# pickit.net
KiCad netlist of a schematic drawn in Altium Designer
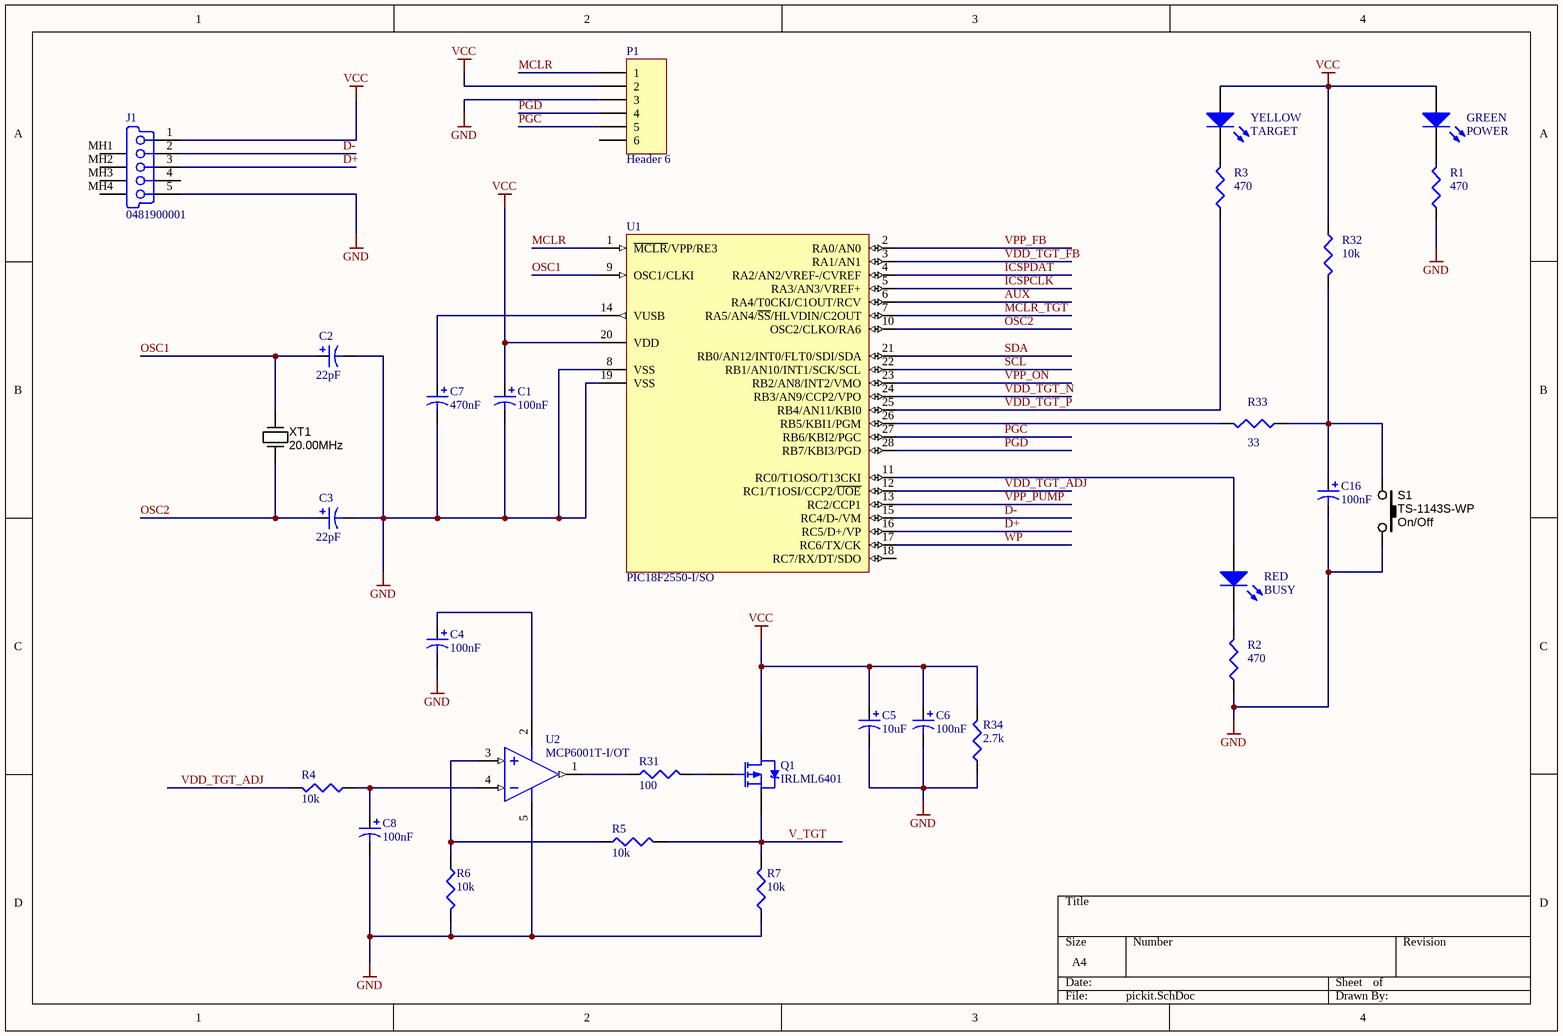
[diagram p0: pickit.SchDoc]

(export (version "E")
  (design (tool "Eeschema 10.0.6"))
  (components
    (comp (ref "C1")
      (value "100nF")
      (footprint "C0805")
      (description "Polarized Capacitor (Surface Mount)")
      (fields (field (name "Comment") "Cap Pol3") (field (name "PUBLISHER") "Altium Limited"))
      (libsource (lib "Miscellaneous Devices") (part "Cap Pol3"))
    )
    (comp (ref "C2")
      (value "22pF")
      (footprint "C0805")
      (description "Polarized Capacitor (Surface Mount)")
      (fields (field (name "Comment") "Cap Pol3") (field (name "PUBLISHER") "Altium Limited"))
      (libsource (lib "Miscellaneous Devices") (part "Cap Pol3"))
    )
    (comp (ref "C3")
      (value "22pF")
      (footprint "C0805")
      (description "Polarized Capacitor (Surface Mount)")
      (fields (field (name "Comment") "Cap Pol3") (field (name "PUBLISHER") "Altium Limited"))
      (libsource (lib "Miscellaneous Devices") (part "Cap Pol3"))
    )
    (comp (ref "C4")
      (value "100nF")
      (footprint "C0805")
      (description "Polarized Capacitor (Surface Mount)")
      (fields (field (name "Comment") "Cap Pol3") (field (name "PUBLISHER") "Altium Limited"))
      (libsource (lib "Miscellaneous Devices") (part "Cap Pol3"))
    )
    (comp (ref "C5")
      (value "10uF")
      (footprint "C0805")
      (description "Polarized Capacitor (Surface Mount)")
      (fields (field (name "Comment") "Cap Pol3") (field (name "PUBLISHER") "Altium Limited"))
      (libsource (lib "Miscellaneous Devices") (part "Cap Pol3"))
    )
    (comp (ref "C6")
      (value "100nF")
      (footprint "C0805")
      (description "Polarized Capacitor (Surface Mount)")
      (fields (field (name "Comment") "Cap Pol3") (field (name "PUBLISHER") "Altium Limited"))
      (libsource (lib "Miscellaneous Devices") (part "Cap Pol3"))
    )
    (comp (ref "C7")
      (value "470nF")
      (footprint "C0805")
      (description "Polarized Capacitor (Surface Mount)")
      (fields (field (name "Comment") "Cap Pol3") (field (name "PUBLISHER") "Altium Limited"))
      (libsource (lib "Miscellaneous Devices") (part "Cap Pol3"))
    )
    (comp (ref "C8")
      (value "100nF")
      (footprint "C0805")
      (description "Polarized Capacitor (Surface Mount)")
      (fields (field (name "Comment") "Cap Pol3") (field (name "PUBLISHER") "Altium Limited"))
      (libsource (lib "Miscellaneous Devices") (part "Cap Pol3"))
    )
    (comp (ref "C16")
      (value "100nF")
      (footprint "C0805")
      (description "Polarized Capacitor (Surface Mount)")
      (fields (field (name "Comment") "Cap Pol3") (field (name "PUBLISHER") "Altium Limited"))
      (libsource (lib "Miscellaneous Devices") (part "Cap Pol3"))
    )
    (comp (ref "GREEN")
      (value "POWER")
      (footprint "3.5X2.8X1.9")
      (description "Typical BLUE SiC LED")
      (fields (field (name "PUBLISHER") "Altium Limited"))
      (libsource (lib "Miscellaneous Devices") (part "LED3"))
    )
    (comp (ref "J1")
      (value "0481900001")
      (footprint "481900001")
      (fields (field (name "PUBLISHER") "Altium Limited"))
      (libsource (lib "Molex Serial Bus Mini USB") (part "0481900001"))
    )
    (comp (ref "P1")
      (value "Header 6")
      (footprint "HDR1X6")
      (description "Header, 6-Pin")
      (fields (field (name "PUBLISHER") "Altium Limited"))
      (libsource (lib "Miscellaneous Connectors") (part "Header 6"))
    )
    (comp (ref "Q1")
      (value "IRLML6401")
      (footprint "Micro3_N")
      (description "HEXFET Power MOSFET")
      (fields (field (name "PUBLISHER") "Altium Limited"))
      (libsource (lib "IR Discrete MOSFET - Power") (part "IRLML6401"))
    )
    (comp (ref "R1")
      (value "470")
      (footprint "RESC2012X70N")
      (description "Resistor")
      (fields (field (name "Comment") "Res3") (field (name "PUBLISHER") "Altium Limited"))
      (libsource (lib "Miscellaneous Devices") (part "Res3"))
    )
    (comp (ref "R2")
      (value "470")
      (footprint "RESC2012X70N")
      (description "Resistor")
      (fields (field (name "Comment") "Res3") (field (name "PUBLISHER") "Altium Limited"))
      (libsource (lib "Miscellaneous Devices") (part "Res3"))
    )
    (comp (ref "R3")
      (value "470")
      (footprint "RESC2012X70N")
      (description "Resistor")
      (fields (field (name "Comment") "Res3") (field (name "PUBLISHER") "Altium Limited"))
      (libsource (lib "Miscellaneous Devices") (part "Res3"))
    )
    (comp (ref "R4")
      (value "10k")
      (footprint "RESC2012X70N")
      (description "Resistor")
      (fields (field (name "Comment") "Res3") (field (name "PUBLISHER") "Altium Limited"))
      (libsource (lib "Miscellaneous Devices") (part "Res3"))
    )
    (comp (ref "R5")
      (value "10k")
      (footprint "RESC2012X70N")
      (description "Resistor")
      (fields (field (name "Comment") "Res3") (field (name "PUBLISHER") "Altium Limited"))
      (libsource (lib "Miscellaneous Devices") (part "Res3"))
    )
    (comp (ref "R6")
      (value "10k")
      (footprint "RESC2012X70N")
      (description "Resistor")
      (fields (field (name "Comment") "Res3") (field (name "PUBLISHER") "Altium Limited"))
      (libsource (lib "Miscellaneous Devices") (part "Res3"))
    )
    (comp (ref "R7")
      (value "10k")
      (footprint "RESC2012X70N")
      (description "Resistor")
      (fields (field (name "Comment") "Res3") (field (name "PUBLISHER") "Altium Limited"))
      (libsource (lib "Miscellaneous Devices") (part "Res3"))
    )
    (comp (ref "R31")
      (value "100")
      (footprint "RESC2012X70N")
      (description "Resistor")
      (fields (field (name "Comment") "Res3") (field (name "PUBLISHER") "Altium Limited"))
      (libsource (lib "Miscellaneous Devices") (part "Res3"))
    )
    (comp (ref "R32")
      (value "10k")
      (footprint "RESC2012X70N")
      (description "Resistor")
      (fields (field (name "Comment") "Res3") (field (name "PUBLISHER") "Altium Limited"))
      (libsource (lib "Miscellaneous Devices") (part "Res3"))
    )
    (comp (ref "R33")
      (value "33")
      (footprint "RESC2012X70N")
      (description "Resistor")
      (fields (field (name "Comment") "Res3") (field (name "PUBLISHER") "Altium Limited"))
      (libsource (lib "Miscellaneous Devices") (part "Res3"))
    )
    (comp (ref "R34")
      (value "2.7k")
      (footprint "RESC2012X70N")
      (description "Resistor")
      (fields (field (name "Comment") "Res3") (field (name "PUBLISHER") "Altium Limited"))
      (libsource (lib "Miscellaneous Devices") (part "Res3"))
    )
    (comp (ref "RED")
      (value "BUSY")
      (footprint "3.5X2.8X1.9")
      (description "Typical BLUE SiC LED")
      (fields (field (name "PUBLISHER") "Altium Limited"))
      (libsource (lib "Miscellaneous Devices") (part "LED3"))
    )
    (comp (ref "S1")
      (value "TS-1143S-WP")
      (footprint "TS-1143S")
      (description "Switch SMD Tact 4.3mm Stem")
      (fields (field (name "FUNCTION") "On/Off"))
      (libsource (lib "PBL - Switches") (part "SW_SMD_PB_4.3mm"))
    )
    (comp (ref "U1")
      (value "PIC18F2550-I/SO")
      (footprint "SOIC-SO28_N")
      (fields (field (name "PUBLISHER") "Altium Limited"))
      (libsource (lib "Microchip Microcontroller 8-Bit PIC18") (part "PIC18F2550-I/SO"))
    )
    (comp (ref "U2")
      (value "MCP6001T-I/OT")
      (footprint "SOT-23-OT5_N")
      (description "1 MHz, Low-Power Operational Amplifier, 5-Pin SOT-23, Industrial Temperature, Tape and Reel")
      (fields (field (name "PUBLISHER") "Altium Limited"))
      (libsource (lib "Microchip Linear Devices") (part "MCP6001T-I/OT"))
    )
    (comp (ref "XT1")
      (value "20.00MHz")
      (footprint "CRYSTAL_HC49-US-SM")
      (description "Resonator Ceramic 6.00 MHz 30ppm")
      (libsource (lib "PBL - Resonators") (part "Crystal_6MHz_HC49/US"))
    )
    (comp (ref "YELLOW")
      (value "TARGET")
      (footprint "3.5X2.8X1.9")
      (description "Typical BLUE SiC LED")
      (fields (field (name "PUBLISHER") "Altium Limited"))
      (libsource (lib "Miscellaneous Devices") (part "LED3"))
    )
  )
  (nets
    (net (code "1") (name "/AUX") (class "Default")
      (node (ref "U1") (pin "6") (pinfunction "RA4/T0CKI/C1OUT/RCV_6") (pintype "bidirectional"))
    )
    (net (code "2") (name "/D+") (class "Default")
      (node (ref "J1") (pin "3") (pinfunction "D+_3") (pintype "passive"))
      (node (ref "U1") (pin "16") (pinfunction "RC5/D+/VP_16") (pintype "bidirectional"))
    )
    (net (code "3") (name "/D-") (class "Default")
      (node (ref "J1") (pin "2") (pinfunction "D-_2") (pintype "passive"))
      (node (ref "U1") (pin "15") (pinfunction "RC4/D-/VM_15") (pintype "bidirectional"))
    )
    (net (code "4") (name "/ICSPCLK") (class "Default")
      (node (ref "U1") (pin "5") (pinfunction "RA3/AN3/VREF+_5") (pintype "bidirectional"))
    )
    (net (code "5") (name "/ICSPDAT") (class "Default")
      (node (ref "U1") (pin "4") (pinfunction "RA2/AN2/VREF-/CVREF_4") (pintype "bidirectional"))
    )
    (net (code "6") (name "/MCLR") (class "Default")
      (node (ref "P1") (pin "1") (pinfunction "1_1") (pintype "passive"))
      (node (ref "U1") (pin "1") (pinfunction "~{MCLR}/VPP/RE3_1") (pintype "input"))
    )
    (net (code "7") (name "/MCLR_TGT") (class "Default")
      (node (ref "U1") (pin "7") (pinfunction "RA5/AN4/~{SS}/HLVDIN/C2OUT_7") (pintype "bidirectional"))
    )
    (net (code "8") (name "/OSC1") (class "Default")
      (node (ref "C2") (pin "1") (pinfunction "1_1") (pintype "passive"))
      (node (ref "U1") (pin "9") (pinfunction "OSC1/CLKI_9") (pintype "input"))
      (node (ref "XT1") (pin "2") (pinfunction "OUT_2") (pintype "passive"))
    )
    (net (code "9") (name "/OSC2") (class "Default")
      (node (ref "C3") (pin "1") (pinfunction "1_1") (pintype "passive"))
      (node (ref "U1") (pin "10") (pinfunction "OSC2/CLKO/RA6_10") (pintype "bidirectional"))
      (node (ref "XT1") (pin "1") (pinfunction "IN_1") (pintype "passive"))
    )
    (net (code "10") (name "/PGC") (class "Default")
      (node (ref "P1") (pin "5") (pinfunction "5_5") (pintype "passive"))
      (node (ref "U1") (pin "27") (pinfunction "RB6/KBI2/PGC_27") (pintype "bidirectional"))
    )
    (net (code "11") (name "/PGD") (class "Default")
      (node (ref "P1") (pin "4") (pinfunction "4_4") (pintype "passive"))
      (node (ref "U1") (pin "28") (pinfunction "RB7/KBI3/PGD_28") (pintype "bidirectional"))
    )
    (net (code "12") (name "/SCL") (class "Default")
      (node (ref "U1") (pin "22") (pinfunction "RB1/AN10/INT1/SCK/SCL_22") (pintype "bidirectional"))
    )
    (net (code "13") (name "/SDA") (class "Default")
      (node (ref "U1") (pin "21") (pinfunction "RB0/AN12/INT0/FLT0/SDI/SDA_21") (pintype "bidirectional"))
    )
    (net (code "14") (name "/VDD_TGT_ADJ") (class "Default")
      (node (ref "R4") (pin "2") (pinfunction "2_2") (pintype "passive"))
      (node (ref "U1") (pin "12") (pinfunction "RC1/T1OSI/CCP2/~{UOE}_12") (pintype "bidirectional"))
    )
    (net (code "15") (name "/VDD_TGT_FB") (class "Default")
      (node (ref "U1") (pin "3") (pinfunction "RA1/AN1_3") (pintype "bidirectional"))
    )
    (net (code "16") (name "/VDD_TGT_N") (class "Default")
      (node (ref "U1") (pin "24") (pinfunction "RB3/AN9/CCP2/VPO_24") (pintype "bidirectional"))
    )
    (net (code "17") (name "/VDD_TGT_P") (class "Default")
      (node (ref "R3") (pin "1") (pinfunction "1_1") (pintype "passive"))
      (node (ref "U1") (pin "25") (pinfunction "RB4/AN11/KBI0_25") (pintype "bidirectional"))
    )
    (net (code "18") (name "/VPP_FB") (class "Default")
      (node (ref "U1") (pin "2") (pinfunction "RA0/AN0_2") (pintype "bidirectional"))
    )
    (net (code "19") (name "/VPP_ON") (class "Default")
      (node (ref "U1") (pin "23") (pinfunction "RB2/AN8/INT2/VMO_23") (pintype "bidirectional"))
    )
    (net (code "20") (name "/VPP_PUMP") (class "Default")
      (node (ref "U1") (pin "13") (pinfunction "RC2/CCP1_13") (pintype "bidirectional"))
    )
    (net (code "21") (name "/V_TGT") (class "Default")
      (node (ref "Q1") (pin "2") (pinfunction "S_2") (pintype "passive"))
      (node (ref "R5") (pin "2") (pinfunction "2_2") (pintype "passive"))
      (node (ref "R7") (pin "2") (pinfunction "2_2") (pintype "passive"))
    )
    (net (code "22") (name "/WP") (class "Default")
      (node (ref "U1") (pin "17") (pinfunction "RC6/TX/CK_17") (pintype "bidirectional"))
    )
    (net (code "23") (name "GND") (class "Default")
      (node (ref "C1") (pin "2") (pinfunction "2_2") (pintype "passive"))
      (node (ref "C16") (pin "2") (pinfunction "2_2") (pintype "passive"))
      (node (ref "C2") (pin "2") (pinfunction "2_2") (pintype "passive"))
      (node (ref "C3") (pin "2") (pinfunction "2_2") (pintype "passive"))
      (node (ref "C4") (pin "2") (pinfunction "2_2") (pintype "passive"))
      (node (ref "C5") (pin "2") (pinfunction "2_2") (pintype "passive"))
      (node (ref "C6") (pin "2") (pinfunction "2_2") (pintype "passive"))
      (node (ref "C7") (pin "2") (pinfunction "2_2") (pintype "passive"))
      (node (ref "C8") (pin "2") (pinfunction "2_2") (pintype "passive"))
      (node (ref "J1") (pin "5") (pinfunction "GND_5") (pintype "passive"))
      (node (ref "P1") (pin "3") (pinfunction "3_3") (pintype "passive"))
      (node (ref "R1") (pin "1") (pinfunction "1_1") (pintype "passive"))
      (node (ref "R2") (pin "1") (pinfunction "1_1") (pintype "passive"))
      (node (ref "R34") (pin "1") (pinfunction "1_1") (pintype "passive"))
      (node (ref "R6") (pin "2") (pinfunction "2_2") (pintype "passive"))
      (node (ref "R7") (pin "1") (pinfunction "1_1") (pintype "passive"))
      (node (ref "S1") (pin "2") (pintype "passive"))
      (node (ref "U1") (pin "19") (pinfunction "VSS_19") (pintype "power_in"))
      (node (ref "U1") (pin "8") (pinfunction "VSS_8") (pintype "power_in"))
      (node (ref "U2") (pin "5") (pinfunction "VDD_5") (pintype "power_in"))
    )
    (net (code "24") (name "Net-(C16-Pad1)") (class "Default")
      (node (ref "C16") (pin "1") (pinfunction "1_1") (pintype "passive"))
      (node (ref "R32") (pin "2") (pinfunction "2_2") (pintype "passive"))
      (node (ref "R33") (pin "1") (pinfunction "1_1") (pintype "passive"))
      (node (ref "S1") (pin "1") (pintype "passive"))
    )
    (net (code "25") (name "Net-(GREEN-K)") (class "Default")
      (node (ref "GREEN") (pin "2") (pinfunction "K_2") (pintype "passive"))
      (node (ref "R1") (pin "2") (pinfunction "2_2") (pintype "passive"))
    )
    (net (code "26") (name "Net-(Q1-G)") (class "Default")
      (node (ref "Q1") (pin "1") (pinfunction "G_1") (pintype "passive"))
      (node (ref "R31") (pin "2") (pinfunction "2_2") (pintype "passive"))
    )
    (net (code "27") (name "Net-(RED-A)") (class "Default")
      (node (ref "RED") (pin "1") (pinfunction "A_1") (pintype "passive"))
      (node (ref "U1") (pin "11") (pinfunction "RC0/T1OSO/T13CKI_11") (pintype "bidirectional"))
    )
    (net (code "28") (name "Net-(RED-K)") (class "Default")
      (node (ref "R2") (pin "2") (pinfunction "2_2") (pintype "passive"))
      (node (ref "RED") (pin "2") (pinfunction "K_2") (pintype "passive"))
    )
    (net (code "29") (name "Net-(U1-RB5{slash}KBI1{slash}PGM)") (class "Default")
      (node (ref "R33") (pin "2") (pinfunction "2_2") (pintype "passive"))
      (node (ref "U1") (pin "26") (pinfunction "RB5/KBI1/PGM_26") (pintype "bidirectional"))
    )
    (net (code "30") (name "Net-(U1-VUSB)") (class "Default")
      (node (ref "C7") (pin "1") (pinfunction "1_1") (pintype "passive"))
      (node (ref "U1") (pin "14") (pinfunction "VUSB_14") (pintype "output"))
    )
    (net (code "31") (name "Net-(U2-VIN+)") (class "Default")
      (node (ref "R5") (pin "1") (pinfunction "1_1") (pintype "passive"))
      (node (ref "R6") (pin "1") (pinfunction "1_1") (pintype "passive"))
      (node (ref "U2") (pin "3") (pinfunction "VIN+_3") (pintype "input"))
    )
    (net (code "32") (name "Net-(U2-VIN-)") (class "Default")
      (node (ref "C8") (pin "1") (pinfunction "1_1") (pintype "passive"))
      (node (ref "R4") (pin "1") (pinfunction "1_1") (pintype "passive"))
      (node (ref "U2") (pin "4") (pinfunction "VIN-_4") (pintype "input"))
    )
    (net (code "33") (name "Net-(U2-VOUT)") (class "Default")
      (node (ref "R31") (pin "1") (pinfunction "1_1") (pintype "passive"))
      (node (ref "U2") (pin "1") (pinfunction "VOUT_1") (pintype "output"))
    )
    (net (code "34") (name "Net-(U2-VSS)") (class "Default")
      (node (ref "C4") (pin "1") (pinfunction "1_1") (pintype "passive"))
      (node (ref "U2") (pin "2") (pinfunction "VSS_2") (pintype "power_in"))
    )
    (net (code "35") (name "Net-(YELLOW-K)") (class "Default")
      (node (ref "R3") (pin "2") (pinfunction "2_2") (pintype "passive"))
      (node (ref "YELLOW") (pin "2") (pinfunction "K_2") (pintype "passive"))
    )
    (net (code "36") (name "VCC") (class "Default")
      (node (ref "C1") (pin "1") (pinfunction "1_1") (pintype "passive"))
      (node (ref "C5") (pin "1") (pinfunction "1_1") (pintype "passive"))
      (node (ref "C6") (pin "1") (pinfunction "1_1") (pintype "passive"))
      (node (ref "GREEN") (pin "1") (pinfunction "A_1") (pintype "passive"))
      (node (ref "J1") (pin "1") (pinfunction "V_BUS_(5V)_1") (pintype "passive"))
      (node (ref "P1") (pin "2") (pinfunction "2_2") (pintype "passive"))
      (node (ref "Q1") (pin "3") (pinfunction "D_3") (pintype "passive"))
      (node (ref "R32") (pin "1") (pinfunction "1_1") (pintype "passive"))
      (node (ref "R34") (pin "2") (pinfunction "2_2") (pintype "passive"))
      (node (ref "U1") (pin "20") (pinfunction "VDD_20") (pintype "power_in"))
      (node (ref "YELLOW") (pin "1") (pinfunction "A_1") (pintype "passive"))
    )
    (net (code "37") (name "unconnected-(J1-NC-Pad4)") (class "Default")
      (node (ref "J1") (pin "4") (pinfunction "NC_4") (pintype "passive"))
    )
    (net (code "38") (name "unconnected-(J1-Tab-PadMH1)") (class "Default")
      (node (ref "J1") (pin "MH1") (pinfunction "Tab_MH1") (pintype "passive"))
    )
    (net (code "39") (name "unconnected-(J1-Tab-PadMH2)") (class "Default")
      (node (ref "J1") (pin "MH2") (pinfunction "Tab_MH2") (pintype "passive"))
    )
    (net (code "40") (name "unconnected-(J1-Tab-PadMH3)") (class "Default")
      (node (ref "J1") (pin "MH3") (pinfunction "Tab_MH3") (pintype "passive"))
    )
    (net (code "41") (name "unconnected-(J1-Tab-PadMH4)") (class "Default")
      (node (ref "J1") (pin "MH4") (pinfunction "Tab_MH4") (pintype "passive"))
    )
    (net (code "42") (name "unconnected-(P1-Pad6)") (class "Default")
      (node (ref "P1") (pin "6") (pinfunction "6_6") (pintype "passive"))
    )
    (net (code "43") (name "unconnected-(U1-RC7{slash}RX{slash}DT{slash}SDO-Pad18)") (class "Default")
      (node (ref "U1") (pin "18") (pinfunction "RC7/RX/DT/SDO_18") (pintype "bidirectional"))
    )
  )
)
